# Power.net
KiCad netlist of a schematic drawn in Altium Designer
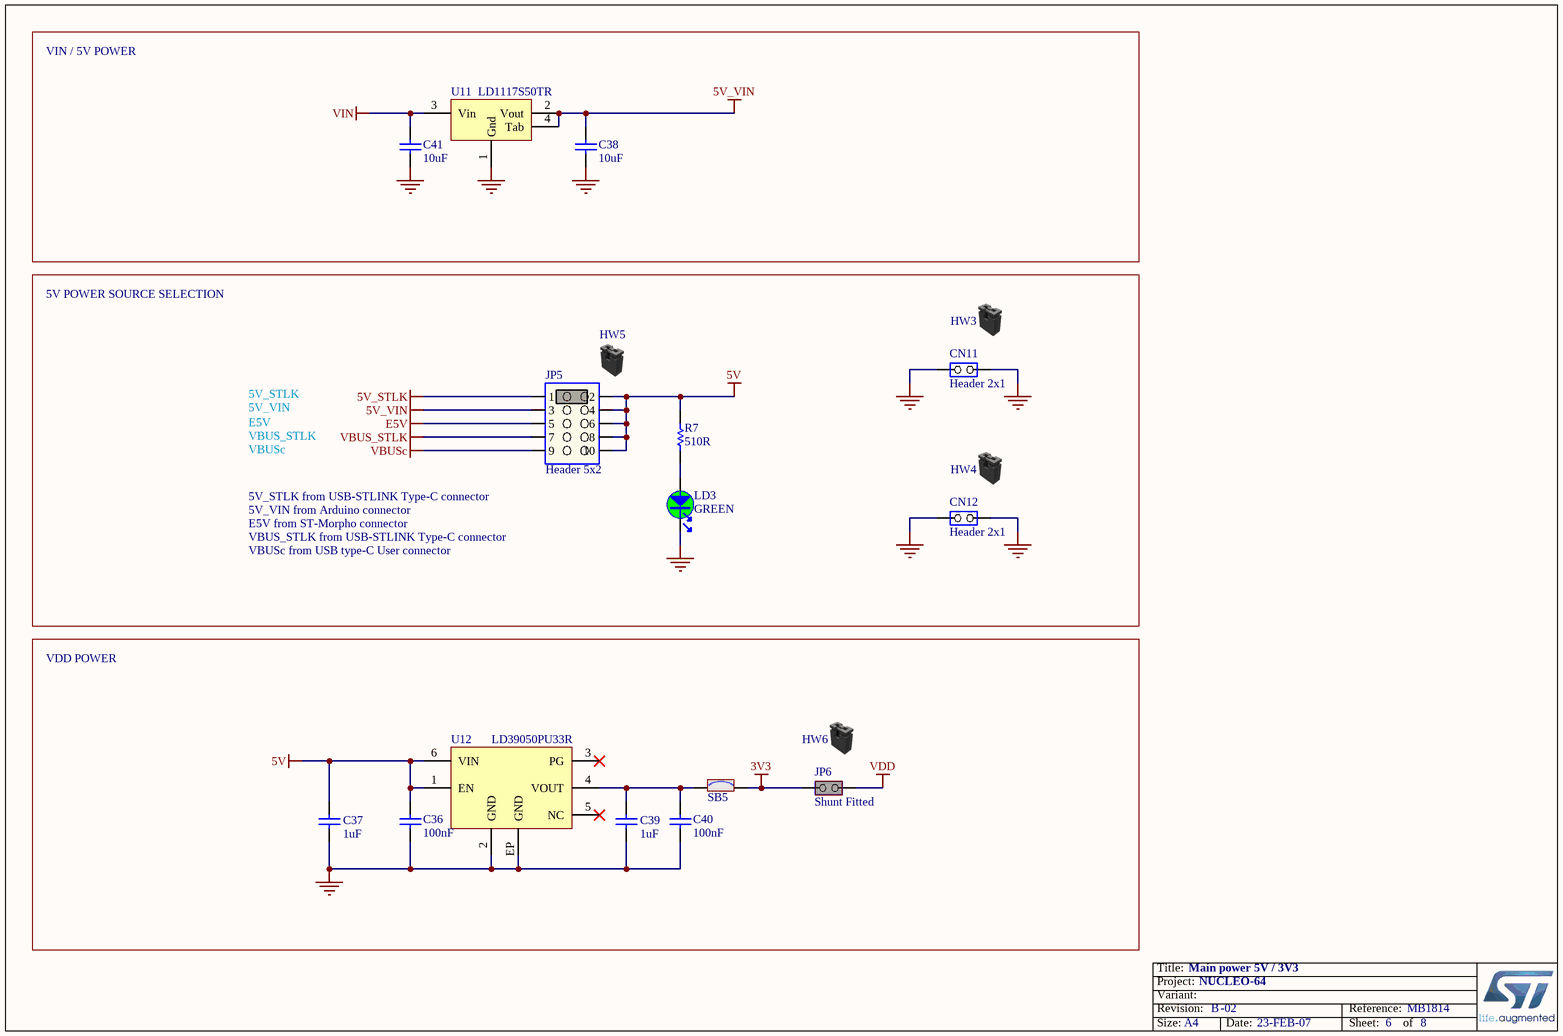
[diagram p0: Power.SchDoc]

(export (version "E")
  (design (tool "Eeschema 10.0.6"))
  (components
    (comp (ref "C36")
      (value "100nF")
      (footprint "C0402")
      (description "Capacitor, MLCC, 100nF, 16V, X7R, 10%, 0402, T=0,5mm")
      (fields
        (field (name "INTERNAL_PART_NUMBER") "MCD-00102")
        (field (name "MANUFACTURER_PART_NUMBER") "CC0402KRX7R7BB104")
        (field (name "PROVIDED_BY") "Subcon")
      )
      (libsource (lib "MCD_PARTS_database") (part "Capacitor"))
    )
    (comp (ref "C37")
      (value "1uF")
      (footprint "C0603")
      (description "Capacitor, MLCC, 1uF, 16V, X5R, 10%, 0603, T=0,8mm")
      (fields
        (field (name "INTERNAL_PART_NUMBER") "MCD-00010")
        (field (name "MANUFACTURER_PART_NUMBER") "CC0603KRX5R7BB105")
        (field (name "PROVIDED_BY") "Subcon")
      )
      (libsource (lib "MCD_PARTS_database") (part "Capacitor"))
    )
    (comp (ref "C38")
      (value "10uF")
      (footprint "C0805")
      (description "Capacitor, MLCC, 10uF, 25V, X5R, 10%, 0805, T=0,85mm")
      (fields
        (field (name "INTERNAL_PART_NUMBER") "MCD-00014")
        (field (name "MANUFACTURER_PART_NUMBER") "CC0805KRX5R8BB106")
        (field (name "PROVIDED_BY") "SUBCO")
      )
      (libsource (lib "MCD_PARTS_database") (part "Capacitor"))
    )
    (comp (ref "C39")
      (value "1uF")
      (footprint "C0603")
      (description "Capacitor, MLCC, 1uF, 16V, X5R, 10%, 0603, T=0,8mm")
      (fields
        (field (name "INTERNAL_PART_NUMBER") "MCD-00010")
        (field (name "MANUFACTURER_PART_NUMBER") "CC0603KRX5R7BB105")
        (field (name "PROVIDED_BY") "Subcon")
      )
      (libsource (lib "MCD_PARTS_database") (part "Capacitor"))
    )
    (comp (ref "C40")
      (value "100nF")
      (footprint "C0402")
      (description "Capacitor, MLCC, 100nF, 16V, X7R, 10%, 0402, T=0,5mm")
      (fields
        (field (name "INTERNAL_PART_NUMBER") "MCD-00102")
        (field (name "MANUFACTURER_PART_NUMBER") "CC0402KRX7R7BB104")
        (field (name "PROVIDED_BY") "Subcon")
      )
      (libsource (lib "MCD_PARTS_database") (part "Capacitor"))
    )
    (comp (ref "C41")
      (value "10uF")
      (footprint "C0805")
      (description "Capacitor, MLCC, 10uF, 25V, X5R, 10%, 0805, T=0,85mm")
      (fields
        (field (name "INTERNAL_PART_NUMBER") "MCD-00014")
        (field (name "MANUFACTURER_PART_NUMBER") "CC0805KRX5R8BB106")
        (field (name "PROVIDED_BY") "SUBCO")
      )
      (libsource (lib "MCD_PARTS_database") (part "Capacitor"))
    )
    (comp (ref "CN11")
      (value "Header 2x1")
      (footprint "CON_SAMTEC_TSW-102-09-X-S")
      (description "Header, 2x1, 2.54mm, VR, TH, T=5.84mm/10.16mm")
      (fields (field (name "INTERNAL_PART_NUMBER") "MCD-00214") (field (name "MANUFACTURER") "SAMTEC"))
      (libsource (lib "MCD_PARTS_database") (part "Jumper_Header 2x1"))
    )
    (comp (ref "CN12")
      (value "Header 2x1")
      (footprint "CON_SAMTEC_TSW-102-09-X-S")
      (description "Header, 2x1, 2.54mm, VR, TH, T=5.84mm/10.16mm")
      (fields (field (name "INTERNAL_PART_NUMBER") "MCD-00214") (field (name "MANUFACTURER") "SAMTEC"))
      (libsource (lib "MCD_PARTS_database") (part "Jumper_Header 2x1"))
    )
    (comp (ref "HW3")
      (value "~")
      (description "SHUNT 2.54mm BLACK")
      (fields
        (field (name "INTERNAL_PART_NUMBER") "MCD-00043")
        (field (name "MANUFACTURER_PART_NUMBER") "SNT-100-BK-G")
        (field (name "PROVIDED_BY") "Subcon")
      )
      (libsource (lib "MCD_PARTS_database") (part "Shunt Black 2.54mm"))
    )
    (comp (ref "HW4")
      (value "~")
      (description "SHUNT 2.54mm BLACK")
      (fields
        (field (name "INTERNAL_PART_NUMBER") "MCD-00043")
        (field (name "MANUFACTURER_PART_NUMBER") "SNT-100-BK-G")
        (field (name "PROVIDED_BY") "Subcon")
      )
      (libsource (lib "MCD_PARTS_database") (part "Shunt Black 2.54mm"))
    )
    (comp (ref "HW5")
      (value "~")
      (description "SHUNT 2.54mm BLACK")
      (fields
        (field (name "INTERNAL_PART_NUMBER") "MCD-00043")
        (field (name "MANUFACTURER_PART_NUMBER") "SNT-100-BK-G")
        (field (name "PROVIDED_BY") "Subcon")
      )
      (libsource (lib "MCD_PARTS_database") (part "Shunt Black 2.54mm"))
    )
    (comp (ref "HW6")
      (value "~")
      (description "SHUNT 2.54mm BLACK")
      (fields
        (field (name "INTERNAL_PART_NUMBER") "MCD-00043")
        (field (name "MANUFACTURER_PART_NUMBER") "SNT-100-BK-G")
        (field (name "PROVIDED_BY") "Subcon")
      )
      (libsource (lib "MCD_PARTS_database") (part "Shunt Black 2.54mm"))
    )
    (comp (ref "JP5")
      (value "Header 5x2")
      (footprint "CON_SAMTEC_TSW-105-07-X-D")
      (description "Header, 5x2, 2.54mm, VR, TH, T=5.84mm/2.54mm")
      (fields (field (name "INTERNAL_PART_NUMBER") "MCD-01203") (field (name "BMS_PART_NUMBER") "9083523"))
      (libsource (lib "MCD_PARTS_database") (part "Jumper_Header 5x2 Fitted 1-2"))
    )
    (comp (ref "JP6")
      (value "Shunt Fitted")
      (footprint "CON_SAMTEC_TSW-102-07-G-S")
      (description "Header, 2x1, 2,54mm, VR, TH, Height 5.84mm/2.54mm - Shunt Fitted by default")
      (fields
        (field (name "INTERNAL_PART_NUMBER") "MCD-00683")
        (field (name "MANUFACTURER_PART_NUMBER") "TSW-102-07-x-S")
        (field (name "PROVIDED_BY") "Subcon")
      )
      (libsource (lib "MCD_PARTS_database") (part "Jumper_Header 2x1 Fitted"))
    )
    (comp (ref "LD3")
      (value "GREEN")
      (footprint "LED_0603_OSRAM_LG-Q396-PS-35_GREEN_1A2K_H0P4")
      (description "LED Green, 0603 SMD, Forward Voltage Typ=2V, Max=2.5V")
      (fields
        (field (name "INTERNAL_PART_NUMBER") "MCD-00588")
        (field (name "MANUFACTURER_PART_NUMBER") "LG Q396-PS-35")
        (field (name "PROVIDED_BY") "SUBCO")
      )
      (libsource (lib "MCD_PARTS_database") (part "LED_green"))
    )
    (comp (ref "R7")
      (value "510R")
      (footprint "R0603")
      (description "Resistor,510R,0603,1%,1/10W")
      (fields
        (field (name "INTERNAL_PART_NUMBER") "MCD-00225")
        (field (name "MANUFACTURER_PART_NUMBER") "RC0603FR-07510RL")
        (field (name "PROVIDED_BY") "SUBCO")
      )
      (libsource (lib "MCD_PARTS_database") (part "Resistor"))
    )
    (comp (ref "SB5")
      (value "~")
      (footprint "SOLDER-BRIDGE_R0603-0R")
      (description "Solder Bridge ON")
      (fields
        (field (name "INTERNAL_PART_NUMBER") "MCD-00071")
        (field (name "MANUFACTURER_PART_NUMBER") "RC0603JR-070RL")
        (field (name "PROVIDED_BY") "SUBCO")
      )
      (libsource (lib "MCD_PARTS_database") (part "SB_ON"))
    )
    (comp (ref "U11")
      (value "LD1117S50TR")
      (footprint "REG_SOT223-TAB")
      (description "IC REG LDO 5V 0.8A SOT223")
      (fields
        (field (name "INTERNAL_PART_NUMBER") "MCD-00088")
        (field (name "MANUFACTURER") "STMICROELECTRONICS")
        (field (name "PROVIDED_BY") "SUBCO with ST control")
      )
      (libsource (lib "MCD_PARTS_database") (part "LD1117S50TR"))
    )
    (comp (ref "U12")
      (value "LD39050PU33R")
      (footprint "ICC_DFN6-EPAD_3X3_P095")
      (description "Low quiescent current and low noise voltage regulators")
      (fields
        (field (name "INTERNAL_PART_NUMBER") "MCD-00215")
        (field (name "MANUFACTURER") "STMICROELECTRONICS")
        (field (name "PROVIDED_BY") "SUBCO with ST control")
      )
      (libsource (lib "MCD_PARTS_database") (part "LD39050PU33R"))
    )
  )
  (nets
    (net (code "1") (name "3V3") (class "Default")
      (node (ref "JP6") (pin "1") (pinfunction "COMMON_1") (pintype "passive"))
      (node (ref "SB5") (pin "2") (pinfunction "2_2") (pintype "passive"))
    )
    (net (code "2") (name "5V") (class "Default")
      (node (ref "C36") (pin "2") (pinfunction "2_2") (pintype "passive"))
      (node (ref "C37") (pin "2") (pinfunction "2_2") (pintype "passive"))
      (node (ref "JP5") (pin "10") (pinfunction "10_10") (pintype "passive"))
      (node (ref "JP5") (pin "2") (pinfunction "2_2") (pintype "passive"))
      (node (ref "JP5") (pin "4") (pinfunction "4_4") (pintype "passive"))
      (node (ref "JP5") (pin "6") (pinfunction "6_6") (pintype "passive"))
      (node (ref "JP5") (pin "8") (pinfunction "8_8") (pintype "passive"))
      (node (ref "R7") (pin "2") (pinfunction "2_2") (pintype "passive"))
      (node (ref "U12") (pin "1") (pinfunction "EN_1") (pintype "passive"))
      (node (ref "U12") (pin "6") (pinfunction "VIN_6") (pintype "passive"))
    )
    (net (code "3") (name "5V_STLK") (class "Default")
      (node (ref "JP5") (pin "1") (pinfunction "1_1") (pintype "passive"))
    )
    (net (code "4") (name "5V_VIN") (class "Default")
      (node (ref "C38") (pin "2") (pinfunction "2_2") (pintype "passive"))
      (node (ref "JP5") (pin "3") (pinfunction "3_3") (pintype "passive"))
      (node (ref "U11") (pin "2") (pinfunction "Vout_2") (pintype "passive"))
      (node (ref "U11") (pin "4") (pinfunction "Tab_4") (pintype "passive"))
    )
    (net (code "5") (name "E5V") (class "Default")
      (node (ref "JP5") (pin "5") (pinfunction "5_5") (pintype "passive"))
    )
    (net (code "6") (name "GND") (class "Default")
      (node (ref "C36") (pin "1") (pinfunction "1_1") (pintype "passive"))
      (node (ref "C37") (pin "1") (pinfunction "1_1") (pintype "passive"))
      (node (ref "C38") (pin "1") (pinfunction "1_1") (pintype "passive"))
      (node (ref "C39") (pin "1") (pinfunction "1_1") (pintype "passive"))
      (node (ref "C40") (pin "1") (pinfunction "1_1") (pintype "passive"))
      (node (ref "C41") (pin "1") (pinfunction "1_1") (pintype "passive"))
      (node (ref "CN11") (pin "1") (pinfunction "COMMON_1") (pintype "passive"))
      (node (ref "CN11") (pin "2") (pinfunction "NO_2") (pintype "passive"))
      (node (ref "CN12") (pin "1") (pinfunction "COMMON_1") (pintype "passive"))
      (node (ref "CN12") (pin "2") (pinfunction "NO_2") (pintype "passive"))
      (node (ref "LD3") (pin "2") (pintype "passive"))
      (node (ref "U11") (pin "1") (pinfunction "Gnd_1") (pintype "passive"))
      (node (ref "U12") (pin "2") (pinfunction "GND_2") (pintype "passive"))
      (node (ref "U12") (pin "EP") (pinfunction "GND_EP") (pintype "passive"))
    )
    (net (code "7") (name "Net-(LD3-Pad1)") (class "Default")
      (node (ref "LD3") (pin "1") (pintype "passive"))
      (node (ref "R7") (pin "1") (pinfunction "1_1") (pintype "passive"))
    )
    (net (code "8") (name "Net-(U12-VOUT)") (class "Default")
      (node (ref "C39") (pin "2") (pinfunction "2_2") (pintype "passive"))
      (node (ref "C40") (pin "2") (pinfunction "2_2") (pintype "passive"))
      (node (ref "SB5") (pin "1") (pinfunction "1_1") (pintype "passive"))
      (node (ref "U12") (pin "4") (pinfunction "VOUT_4") (pintype "passive"))
    )
    (net (code "9") (name "VBUS_STLK") (class "Default")
      (node (ref "JP5") (pin "7") (pinfunction "7_7") (pintype "passive"))
    )
    (net (code "10") (name "VBUSc") (class "Default")
      (node (ref "JP5") (pin "9") (pinfunction "9_9") (pintype "passive"))
    )
    (net (code "11") (name "VDD") (class "Default")
      (node (ref "JP6") (pin "2") (pinfunction "NO_2") (pintype "passive"))
    )
    (net (code "12") (name "VIN") (class "Default")
      (node (ref "C41") (pin "2") (pinfunction "2_2") (pintype "passive"))
      (node (ref "U11") (pin "3") (pinfunction "Vin_3") (pintype "passive"))
    )
    (net (code "13") (name "unconnected-(U12-NC-Pad5)") (class "Default")
      (node (ref "U12") (pin "5") (pinfunction "NC_5") (pintype "passive+no_connect"))
    )
    (net (code "14") (name "unconnected-(U12-PG-Pad3)") (class "Default")
      (node (ref "U12") (pin "3") (pinfunction "PG_3") (pintype "passive+no_connect"))
    )
  )
)
